# 05__Control_Panel_Items_Sheet.net
KiCad netlist of a schematic drawn in Altium Designer
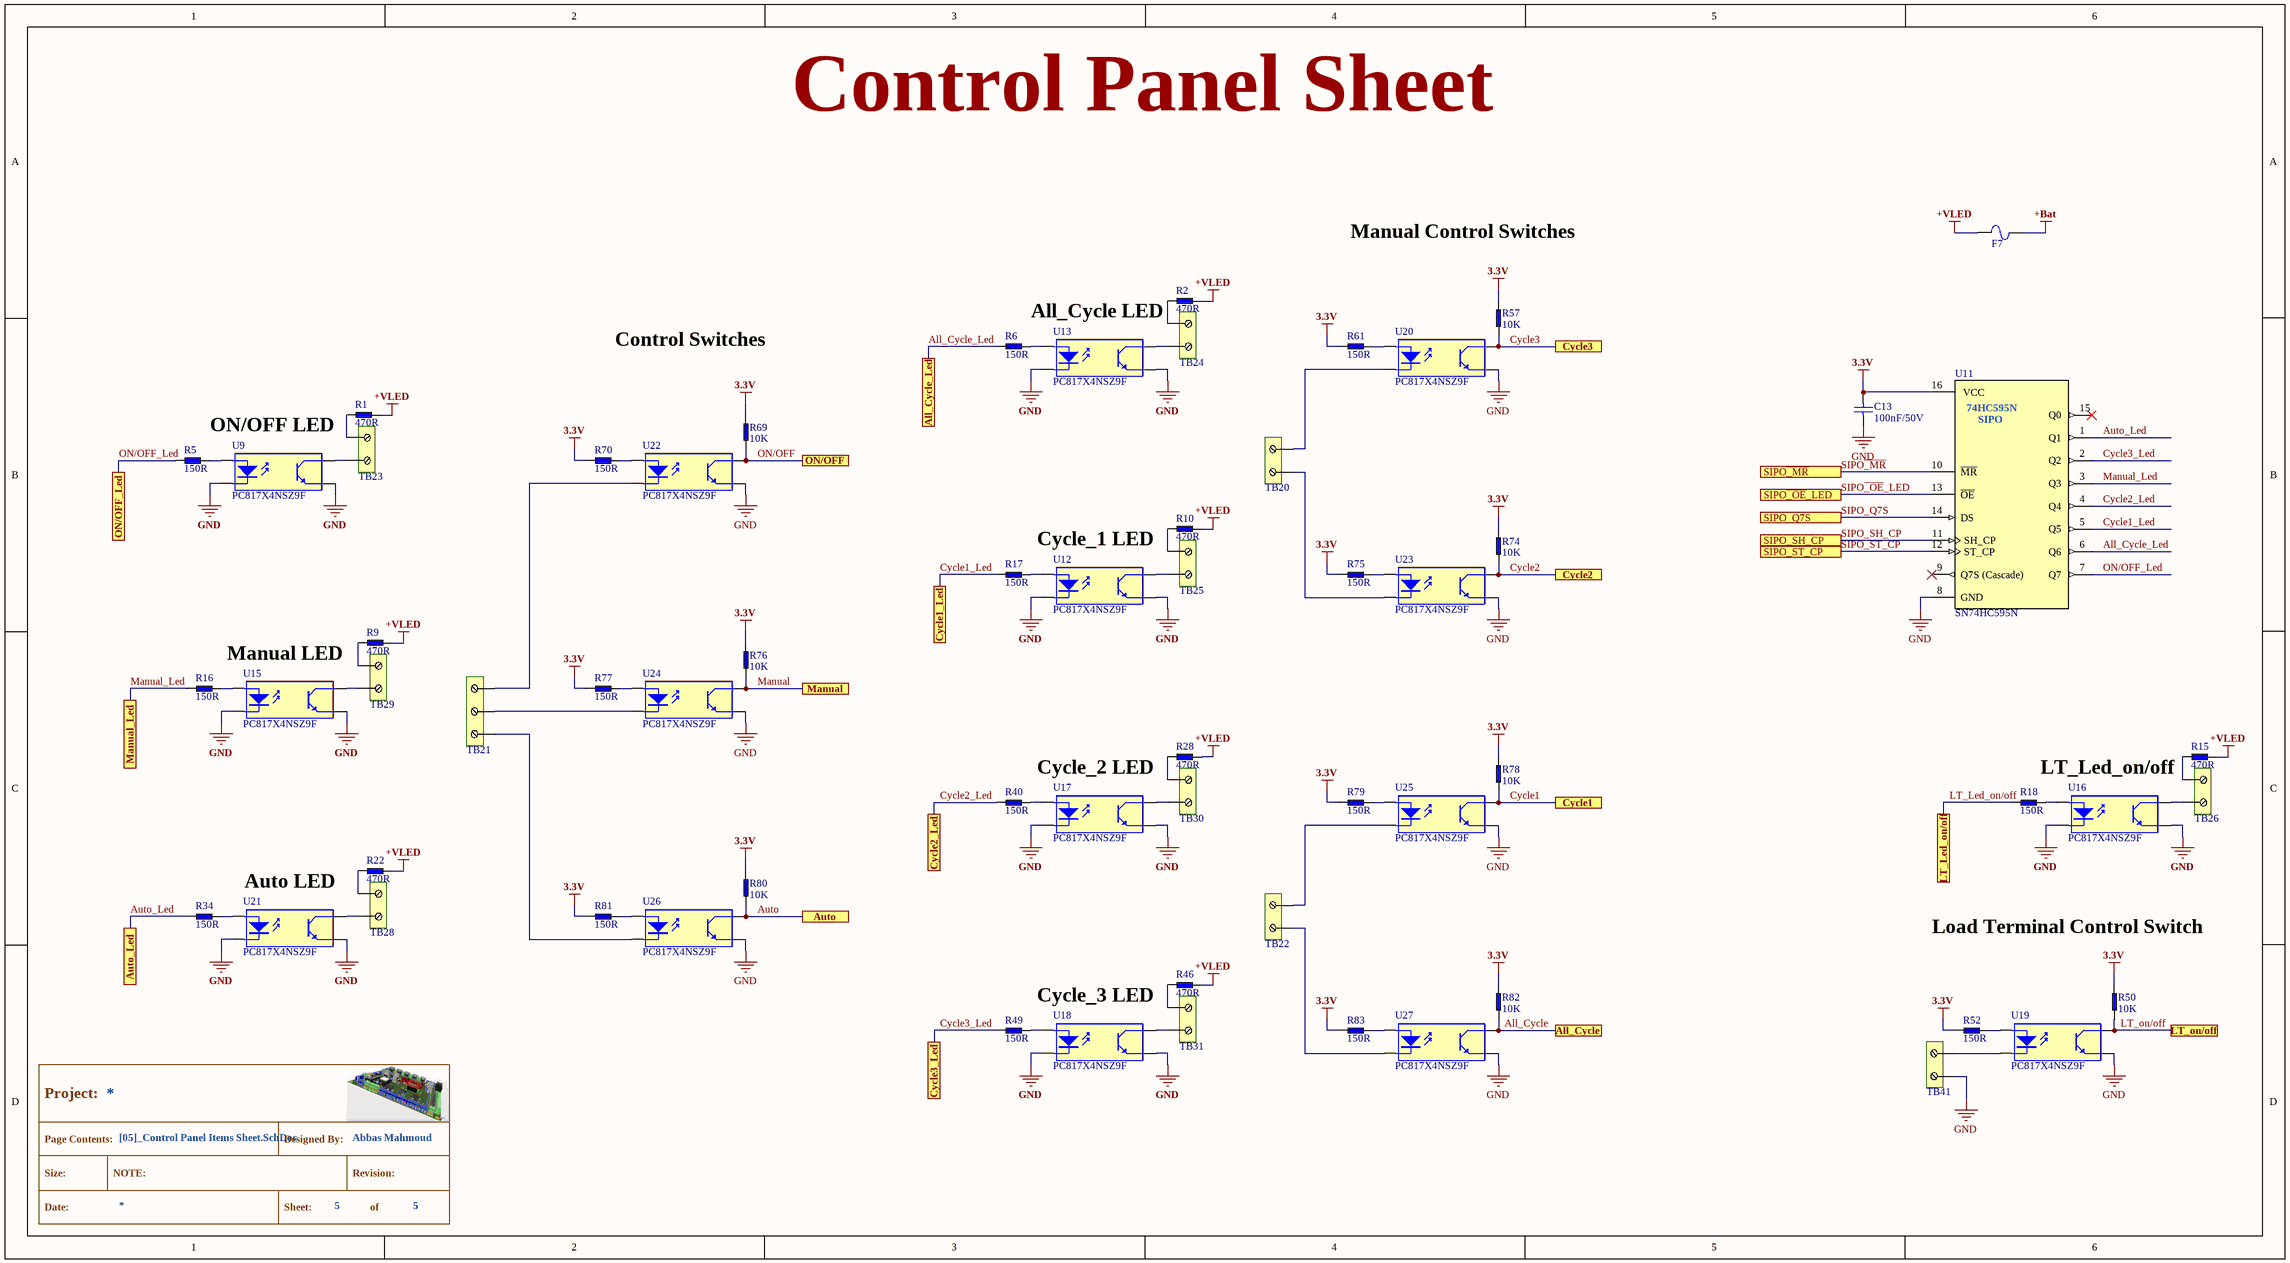
[diagram p0: [05]_Control Panel Items Sheet.SchDoc]

(export (version "E")
  (design (tool "Eeschema 10.0.6"))
  (components
    (comp (ref "*")
      (value "Title Block")
      (description "Moatley Title Block")
      (libsource (lib "Altium_Abbas") (part "Title Block"))
    )
    (comp (ref "C13")
      (value "100nF/50V")
      (footprint "CCAP - PACKAGE - THT ,P = 2.54 MM")
      (description "100nF -20%~+80% 50V Through Hole,P=2.54mm Ceramic Disc Capacitors RoHS")
      (libsource (lib "Altium_Abbas_V3") (part "CCAP - 100nF - 50V - THT - P = 2.54"))
    )
    (comp (ref "F7")
      (value "FUSES&HOLDERS")
      (footprint "FUSE-BLX-A HOLDER")
      (libsource (lib "Altium_Abbas_V3") (part "FUSES&HOLDERS"))
    )
    (comp (ref "R1")
      (value "470R")
      (footprint "R - THT - P5.0 - 1/4W")
      (description "470R ±1% 1/4W ±100ppm/℃ Axial Metal Film Resistor_ Throuh Hole Technology RoHS")
      (libsource (lib "Altium_Abbas_V3") (part "R470R - THT"))
    )
    (comp (ref "R2")
      (value "470R")
      (footprint "R - THT - P5.0 - 1/4W")
      (description "470R ±1% 1/4W ±100ppm/℃ Axial Metal Film Resistor_ Throuh Hole Technology RoHS")
      (libsource (lib "Altium_Abbas_V3") (part "R470R - THT"))
    )
    (comp (ref "R5")
      (value "150R")
      (footprint "R - THT - P5.0 - 1/4W")
      (description "150R ±1% 1/4W ±100ppm/℃ Axial Metal Film Resistor_ Throuh Hole Technology RoHS")
      (libsource (lib "Altium_Abbas_V3") (part "R150R - THT"))
    )
    (comp (ref "R6")
      (value "150R")
      (footprint "R - THT - P5.0 - 1/4W")
      (description "150R ±1% 1/4W ±100ppm/℃ Axial Metal Film Resistor_ Throuh Hole Technology RoHS")
      (libsource (lib "Altium_Abbas_V3") (part "R150R - THT"))
    )
    (comp (ref "R9")
      (value "470R")
      (footprint "R - THT - P5.0 - 1/4W")
      (description "470R ±1% 1/4W ±100ppm/℃ Axial Metal Film Resistor_ Throuh Hole Technology RoHS")
      (libsource (lib "Altium_Abbas_V3") (part "R470R - THT"))
    )
    (comp (ref "R10")
      (value "470R")
      (footprint "R - THT - P5.0 - 1/4W")
      (description "470R ±1% 1/4W ±100ppm/℃ Axial Metal Film Resistor_ Throuh Hole Technology RoHS")
      (libsource (lib "Altium_Abbas_V3") (part "R470R - THT"))
    )
    (comp (ref "R15")
      (value "470R")
      (footprint "R - THT - P5.0 - 1/4W")
      (description "470R ±1% 1/4W ±100ppm/℃ Axial Metal Film Resistor_ Throuh Hole Technology RoHS")
      (libsource (lib "Altium_Abbas_V3") (part "R470R - THT"))
    )
    (comp (ref "R16")
      (value "150R")
      (footprint "R - THT - P5.0 - 1/4W")
      (description "150R ±1% 1/4W ±100ppm/℃ Axial Metal Film Resistor_ Throuh Hole Technology RoHS")
      (libsource (lib "Altium_Abbas_V3") (part "R150R - THT"))
    )
    (comp (ref "R17")
      (value "150R")
      (footprint "R - THT - P5.0 - 1/4W")
      (description "150R ±1% 1/4W ±100ppm/℃ Axial Metal Film Resistor_ Throuh Hole Technology RoHS")
      (libsource (lib "Altium_Abbas_V3") (part "R150R - THT"))
    )
    (comp (ref "R18")
      (value "150R")
      (footprint "R - THT - P5.0 - 1/4W")
      (description "150R ±1% 1/4W ±100ppm/℃ Axial Metal Film Resistor_ Throuh Hole Technology RoHS")
      (libsource (lib "Altium_Abbas_V3") (part "R150R - THT"))
    )
    (comp (ref "R22")
      (value "470R")
      (footprint "R - THT - P5.0 - 1/4W")
      (description "470R ±1% 1/4W ±100ppm/℃ Axial Metal Film Resistor_ Throuh Hole Technology RoHS")
      (libsource (lib "Altium_Abbas_V3") (part "R470R - THT"))
    )
    (comp (ref "R28")
      (value "470R")
      (footprint "R - THT - P5.0 - 1/4W")
      (description "470R ±1% 1/4W ±100ppm/℃ Axial Metal Film Resistor_ Throuh Hole Technology RoHS")
      (libsource (lib "Altium_Abbas_V3") (part "R470R - THT"))
    )
    (comp (ref "R34")
      (value "150R")
      (footprint "R - THT - P5.0 - 1/4W")
      (description "150R ±1% 1/4W ±100ppm/℃ Axial Metal Film Resistor_ Throuh Hole Technology RoHS")
      (libsource (lib "Altium_Abbas_V3") (part "R150R - THT"))
    )
    (comp (ref "R40")
      (value "150R")
      (footprint "R - THT - P5.0 - 1/4W")
      (description "150R ±1% 1/4W ±100ppm/℃ Axial Metal Film Resistor_ Throuh Hole Technology RoHS")
      (libsource (lib "Altium_Abbas_V3") (part "R150R - THT"))
    )
    (comp (ref "R46")
      (value "470R")
      (footprint "R - THT - P5.0 - 1/4W")
      (description "470R ±1% 1/4W ±100ppm/℃ Axial Metal Film Resistor_ Throuh Hole Technology RoHS")
      (libsource (lib "Altium_Abbas_V3") (part "R470R - THT"))
    )
    (comp (ref "R49")
      (value "150R")
      (footprint "R - THT - P5.0 - 1/4W")
      (description "150R ±1% 1/4W ±100ppm/℃ Axial Metal Film Resistor_ Throuh Hole Technology RoHS")
      (libsource (lib "Altium_Abbas_V3") (part "R150R - THT"))
    )
    (comp (ref "R50")
      (value "10K")
      (footprint "R - THT - P5.0 - 1/4W")
      (description "10K ±1% 1/4W ±100ppm/℃ Axial Metal Film Resistor_ Throuh Hole Technology RoHS")
      (libsource (lib "Altium_Abbas_V3") (part "R10K - THT"))
    )
    (comp (ref "R52")
      (value "150R")
      (footprint "R - THT - P5.0 - 1/4W")
      (description "150R ±1% 1/4W ±100ppm/℃ Axial Metal Film Resistor_ Throuh Hole Technology RoHS")
      (libsource (lib "Altium_Abbas_V3") (part "R150R - THT"))
    )
    (comp (ref "R57")
      (value "10K")
      (footprint "R - THT - P5.0 - 1/4W")
      (description "10K ±1% 1/4W ±100ppm/℃ Axial Metal Film Resistor_ Throuh Hole Technology RoHS")
      (libsource (lib "Altium_Abbas_V3") (part "R10K - THT"))
    )
    (comp (ref "R61")
      (value "150R")
      (footprint "R - THT - P5.0 - 1/4W")
      (description "150R ±1% 1/4W ±100ppm/℃ Axial Metal Film Resistor_ Throuh Hole Technology RoHS")
      (libsource (lib "Altium_Abbas_V3") (part "R150R - THT"))
    )
    (comp (ref "R69")
      (value "10K")
      (footprint "R - THT - P5.0 - 1/4W")
      (description "10K ±1% 1/4W ±100ppm/℃ Axial Metal Film Resistor_ Throuh Hole Technology RoHS")
      (libsource (lib "Altium_Abbas_V3") (part "R10K - THT"))
    )
    (comp (ref "R70")
      (value "150R")
      (footprint "R - THT - P5.0 - 1/4W")
      (description "150R ±1% 1/4W ±100ppm/℃ Axial Metal Film Resistor_ Throuh Hole Technology RoHS")
      (libsource (lib "Altium_Abbas_V3") (part "R150R - THT"))
    )
    (comp (ref "R74")
      (value "10K")
      (footprint "R - THT - P5.0 - 1/4W")
      (description "10K ±1% 1/4W ±100ppm/℃ Axial Metal Film Resistor_ Throuh Hole Technology RoHS")
      (libsource (lib "Altium_Abbas_V3") (part "R10K - THT"))
    )
    (comp (ref "R75")
      (value "150R")
      (footprint "R - THT - P5.0 - 1/4W")
      (description "150R ±1% 1/4W ±100ppm/℃ Axial Metal Film Resistor_ Throuh Hole Technology RoHS")
      (libsource (lib "Altium_Abbas_V3") (part "R150R - THT"))
    )
    (comp (ref "R76")
      (value "10K")
      (footprint "R - THT - P5.0 - 1/4W")
      (description "10K ±1% 1/4W ±100ppm/℃ Axial Metal Film Resistor_ Throuh Hole Technology RoHS")
      (libsource (lib "Altium_Abbas_V3") (part "R10K - THT"))
    )
    (comp (ref "R77")
      (value "150R")
      (footprint "R - THT - P5.0 - 1/4W")
      (description "150R ±1% 1/4W ±100ppm/℃ Axial Metal Film Resistor_ Throuh Hole Technology RoHS")
      (libsource (lib "Altium_Abbas_V3") (part "R150R - THT"))
    )
    (comp (ref "R78")
      (value "10K")
      (footprint "R - THT - P5.0 - 1/4W")
      (description "10K ±1% 1/4W ±100ppm/℃ Axial Metal Film Resistor_ Throuh Hole Technology RoHS")
      (libsource (lib "Altium_Abbas_V3") (part "R10K - THT"))
    )
    (comp (ref "R79")
      (value "150R")
      (footprint "R - THT - P5.0 - 1/4W")
      (description "150R ±1% 1/4W ±100ppm/℃ Axial Metal Film Resistor_ Throuh Hole Technology RoHS")
      (libsource (lib "Altium_Abbas_V3") (part "R150R - THT"))
    )
    (comp (ref "R80")
      (value "10K")
      (footprint "R - THT - P5.0 - 1/4W")
      (description "10K ±1% 1/4W ±100ppm/℃ Axial Metal Film Resistor_ Throuh Hole Technology RoHS")
      (libsource (lib "Altium_Abbas_V3") (part "R10K - THT"))
    )
    (comp (ref "R81")
      (value "150R")
      (footprint "R - THT - P5.0 - 1/4W")
      (description "150R ±1% 1/4W ±100ppm/℃ Axial Metal Film Resistor_ Throuh Hole Technology RoHS")
      (libsource (lib "Altium_Abbas_V3") (part "R150R - THT"))
    )
    (comp (ref "R82")
      (value "10K")
      (footprint "R - THT - P5.0 - 1/4W")
      (description "10K ±1% 1/4W ±100ppm/℃ Axial Metal Film Resistor_ Throuh Hole Technology RoHS")
      (libsource (lib "Altium_Abbas_V3") (part "R10K - THT"))
    )
    (comp (ref "R83")
      (value "150R")
      (footprint "R - THT - P5.0 - 1/4W")
      (description "150R ±1% 1/4W ±100ppm/℃ Axial Metal Film Resistor_ Throuh Hole Technology RoHS")
      (libsource (lib "Altium_Abbas_V3") (part "R150R - THT"))
    )
    (comp (ref "TB20")
      (value "2 Pins Pluggable")
      (footprint "TERMINAL BLOCK - 2 PINS - PACKAGE - PLUGGABLE - THT - P = 5.08MM - Horizontal _ Plug+Receptable")
      (libsource (lib "") (part "Terminal Block - 2 Pins - Pluggable_1"))
    )
    (comp (ref "TB21")
      (value "3 Pins Pluggable")
      (footprint "TERMINAL BLOCK - 3 PINS - PACKAGE - PLUGGABLE - THT - P = 5.08MM - HORIZONTAL _ PLUG+RECEPTABLE")
      (libsource (lib "Altium_Abbas_V3") (part "Terminal Block - 3 Pins - Pluggable"))
    )
    (comp (ref "TB22")
      (value "2 Pins Pluggable")
      (footprint "TERMINAL BLOCK - 2 PINS - PACKAGE - PLUGGABLE - THT - P = 5.08MM - Horizontal _ Plug+Receptable")
      (libsource (lib "") (part "Terminal Block - 2 Pins - Pluggable_1"))
    )
    (comp (ref "TB23")
      (value "2 Pins Pluggable")
      (footprint "TERMINAL BLOCK - 2 PINS - PACKAGE - PLUGGABLE - THT - P = 5.08MM - Horizontal _ Plug+Receptable")
      (libsource (lib "Altium_Abbas_V3") (part "Terminal Block - 2 Pins - Pluggable"))
    )
    (comp (ref "TB24")
      (value "2 Pins Pluggable")
      (footprint "TERMINAL BLOCK - 2 PINS - PACKAGE - PLUGGABLE - THT - P = 5.08MM - Horizontal _ Plug+Receptable")
      (libsource (lib "Altium_Abbas_V3") (part "Terminal Block - 2 Pins - Pluggable"))
    )
    (comp (ref "TB25")
      (value "2 Pins Pluggable")
      (footprint "TERMINAL BLOCK - 2 PINS - PACKAGE - PLUGGABLE - THT - P = 5.08MM - Horizontal _ Plug+Receptable")
      (libsource (lib "Altium_Abbas_V3") (part "Terminal Block - 2 Pins - Pluggable"))
    )
    (comp (ref "TB26")
      (value "2 Pins Pluggable")
      (footprint "TERMINAL BLOCK - 2 PINS - PACKAGE - PLUGGABLE - THT - P = 5.08MM - Horizontal _ Plug+Receptable")
      (libsource (lib "Altium_Abbas_V3") (part "Terminal Block - 2 Pins - Pluggable"))
    )
    (comp (ref "TB28")
      (value "2 Pins Pluggable")
      (footprint "TERMINAL BLOCK - 2 PINS - PACKAGE - PLUGGABLE - THT - P = 5.08MM - Horizontal _ Plug+Receptable")
      (libsource (lib "Altium_Abbas_V3") (part "Terminal Block - 2 Pins - Pluggable"))
    )
    (comp (ref "TB29")
      (value "2 Pins Pluggable")
      (footprint "TERMINAL BLOCK - 2 PINS - PACKAGE - PLUGGABLE - THT - P = 5.08MM - Horizontal _ Plug+Receptable")
      (libsource (lib "Altium_Abbas_V3") (part "Terminal Block - 2 Pins - Pluggable"))
    )
    (comp (ref "TB30")
      (value "2 Pins Pluggable")
      (footprint "TERMINAL BLOCK - 2 PINS - PACKAGE - PLUGGABLE - THT - P = 5.08MM - Horizontal _ Plug+Receptable")
      (libsource (lib "Altium_Abbas_V3") (part "Terminal Block - 2 Pins - Pluggable"))
    )
    (comp (ref "TB31")
      (value "2 Pins Pluggable")
      (footprint "TERMINAL BLOCK - 2 PINS - PACKAGE - PLUGGABLE - THT - P = 5.08MM - Horizontal _ Plug+Receptable")
      (libsource (lib "Altium_Abbas_V3") (part "Terminal Block - 2 Pins - Pluggable"))
    )
    (comp (ref "TB41")
      (value "2 Pins Pluggable")
      (footprint "TERMINAL BLOCK - 2 PINS - PACKAGE - PLUGGABLE - THT - P = 5.08MM - Horizontal _ Plug+Receptable")
      (libsource (lib "") (part "Terminal Block - 2 Pins - Pluggable_1"))
    )
    (comp (ref "U9")
      (value "PC817X4NSZ9F")
      (footprint "ICB - DIP-4")
      (description "Optoisolator Transistor Output 5000Vrms 1 Channel 4-DIP")
      (fields (field (name "MANUFACTURER") "Sharp Microelectronics"))
      (libsource (lib "Altium_Abbas_V3") (part "IC - PC817X4NSZ9F"))
    )
    (comp (ref "U11")
      (value "SN74HC595N")
      (footprint "ICB - DIP-16")
      (description "Serial to Parallel or Serial Shift Register Supplementary type DIP-16 Shift Registers RoHS")
      (fields (field (name "MANUFACTURER") "Texas Instruments"))
      (libsource (lib "Altium_Abbas_V3") (part "IC - SN74HC595N"))
    )
    (comp (ref "U12")
      (value "PC817X4NSZ9F")
      (footprint "ICB - DIP-4")
      (description "Optoisolator Transistor Output 5000Vrms 1 Channel 4-DIP")
      (fields (field (name "MANUFACTURER") "Sharp Microelectronics"))
      (libsource (lib "Altium_Abbas_V3") (part "IC - PC817X4NSZ9F"))
    )
    (comp (ref "U13")
      (value "PC817X4NSZ9F")
      (footprint "ICB - DIP-4")
      (description "Optoisolator Transistor Output 5000Vrms 1 Channel 4-DIP")
      (fields (field (name "MANUFACTURER") "Sharp Microelectronics"))
      (libsource (lib "Altium_Abbas_V3") (part "IC - PC817X4NSZ9F"))
    )
    (comp (ref "U15")
      (value "PC817X4NSZ9F")
      (footprint "ICB - DIP-4")
      (description "Optoisolator Transistor Output 5000Vrms 1 Channel 4-DIP")
      (fields (field (name "MANUFACTURER") "Sharp Microelectronics"))
      (libsource (lib "Altium_Abbas_V3") (part "IC - PC817X4NSZ9F"))
    )
    (comp (ref "U16")
      (value "PC817X4NSZ9F")
      (footprint "ICB - DIP-4")
      (description "Optoisolator Transistor Output 5000Vrms 1 Channel 4-DIP")
      (fields (field (name "MANUFACTURER") "Sharp Microelectronics"))
      (libsource (lib "Altium_Abbas_V3") (part "IC - PC817X4NSZ9F"))
    )
    (comp (ref "U17")
      (value "PC817X4NSZ9F")
      (footprint "ICB - DIP-4")
      (description "Optoisolator Transistor Output 5000Vrms 1 Channel 4-DIP")
      (fields (field (name "MANUFACTURER") "Sharp Microelectronics"))
      (libsource (lib "Altium_Abbas_V3") (part "IC - PC817X4NSZ9F"))
    )
    (comp (ref "U18")
      (value "PC817X4NSZ9F")
      (footprint "ICB - DIP-4")
      (description "Optoisolator Transistor Output 5000Vrms 1 Channel 4-DIP")
      (fields (field (name "MANUFACTURER") "Sharp Microelectronics"))
      (libsource (lib "Altium_Abbas_V3") (part "IC - PC817X4NSZ9F"))
    )
    (comp (ref "U19")
      (value "PC817X4NSZ9F")
      (footprint "ICB - DIP-4")
      (description "Optoisolator Transistor Output 5000Vrms 1 Channel 4-DIP")
      (fields (field (name "MANUFACTURER") "Sharp Microelectronics"))
      (libsource (lib "Altium_Abbas_V3") (part "IC - PC817X4NSZ9F"))
    )
    (comp (ref "U20")
      (value "PC817X4NSZ9F")
      (footprint "ICB - DIP-4")
      (description "Optoisolator Transistor Output 5000Vrms 1 Channel 4-DIP")
      (fields (field (name "MANUFACTURER") "Sharp Microelectronics"))
      (libsource (lib "Altium_Abbas_V3") (part "IC - PC817X4NSZ9F"))
    )
    (comp (ref "U21")
      (value "PC817X4NSZ9F")
      (footprint "ICB - DIP-4")
      (description "Optoisolator Transistor Output 5000Vrms 1 Channel 4-DIP")
      (fields (field (name "MANUFACTURER") "Sharp Microelectronics"))
      (libsource (lib "Altium_Abbas_V3") (part "IC - PC817X4NSZ9F"))
    )
    (comp (ref "U22")
      (value "PC817X4NSZ9F")
      (footprint "ICB - DIP-4")
      (description "Optoisolator Transistor Output 5000Vrms 1 Channel 4-DIP")
      (fields (field (name "MANUFACTURER") "Sharp Microelectronics"))
      (libsource (lib "Altium_Abbas_V3") (part "IC - PC817X4NSZ9F"))
    )
    (comp (ref "U23")
      (value "PC817X4NSZ9F")
      (footprint "ICB - DIP-4")
      (description "Optoisolator Transistor Output 5000Vrms 1 Channel 4-DIP")
      (fields (field (name "MANUFACTURER") "Sharp Microelectronics"))
      (libsource (lib "Altium_Abbas_V3") (part "IC - PC817X4NSZ9F"))
    )
    (comp (ref "U24")
      (value "PC817X4NSZ9F")
      (footprint "ICB - DIP-4")
      (description "Optoisolator Transistor Output 5000Vrms 1 Channel 4-DIP")
      (fields (field (name "MANUFACTURER") "Sharp Microelectronics"))
      (libsource (lib "Altium_Abbas_V3") (part "IC - PC817X4NSZ9F"))
    )
    (comp (ref "U25")
      (value "PC817X4NSZ9F")
      (footprint "ICB - DIP-4")
      (description "Optoisolator Transistor Output 5000Vrms 1 Channel 4-DIP")
      (fields (field (name "MANUFACTURER") "Sharp Microelectronics"))
      (libsource (lib "Altium_Abbas_V3") (part "IC - PC817X4NSZ9F"))
    )
    (comp (ref "U26")
      (value "PC817X4NSZ9F")
      (footprint "ICB - DIP-4")
      (description "Optoisolator Transistor Output 5000Vrms 1 Channel 4-DIP")
      (fields (field (name "MANUFACTURER") "Sharp Microelectronics"))
      (libsource (lib "Altium_Abbas_V3") (part "IC - PC817X4NSZ9F"))
    )
    (comp (ref "U27")
      (value "PC817X4NSZ9F")
      (footprint "ICB - DIP-4")
      (description "Optoisolator Transistor Output 5000Vrms 1 Channel 4-DIP")
      (fields (field (name "MANUFACTURER") "Sharp Microelectronics"))
      (libsource (lib "Altium_Abbas_V3") (part "IC - PC817X4NSZ9F"))
    )
  )
  (nets
    (net (code "1") (name "+Bat") (class "Default") (node (ref "F7") (pin "2") (pintype "passive")))
    (net (code "2") (name "+VLED") (class "Default")
      (node (ref "F7") (pin "1") (pintype "passive"))
      (node (ref "R1") (pin "2") (pinfunction "6_2") (pintype "passive"))
      (node (ref "R10") (pin "2") (pinfunction "6_2") (pintype "passive"))
      (node (ref "R15") (pin "2") (pinfunction "6_2") (pintype "passive"))
      (node (ref "R2") (pin "2") (pinfunction "6_2") (pintype "passive"))
      (node (ref "R22") (pin "2") (pinfunction "6_2") (pintype "passive"))
      (node (ref "R28") (pin "2") (pinfunction "6_2") (pintype "passive"))
      (node (ref "R46") (pin "2") (pinfunction "6_2") (pintype "passive"))
      (node (ref "R9") (pin "2") (pinfunction "6_2") (pintype "passive"))
    )
    (net (code "3") (name "/All_Cycle") (class "Default")
      (node (ref "R82") (pin "1") (pinfunction "5_1") (pintype "passive"))
      (node (ref "U27") (pin "4") (pinfunction "C_4") (pintype "passive"))
    )
    (net (code "4") (name "/All_Cycle_Led") (class "Default")
      (node (ref "R6") (pin "1") (pinfunction "5_1") (pintype "passive"))
      (node (ref "U11") (pin "6") (pinfunction "Q6_6") (pintype "output"))
    )
    (net (code "5") (name "/Auto") (class "Default")
      (node (ref "R80") (pin "1") (pinfunction "5_1") (pintype "passive"))
      (node (ref "U26") (pin "4") (pinfunction "C_4") (pintype "passive"))
    )
    (net (code "6") (name "/Auto_Led") (class "Default")
      (node (ref "R34") (pin "1") (pinfunction "5_1") (pintype "passive"))
      (node (ref "U11") (pin "1") (pinfunction "Q1_1") (pintype "output"))
    )
    (net (code "7") (name "/Cycle1") (class "Default")
      (node (ref "R78") (pin "1") (pinfunction "5_1") (pintype "passive"))
      (node (ref "U25") (pin "4") (pinfunction "C_4") (pintype "passive"))
    )
    (net (code "8") (name "/Cycle1_Led") (class "Default")
      (node (ref "R17") (pin "1") (pinfunction "5_1") (pintype "passive"))
      (node (ref "U11") (pin "5") (pinfunction "Q5_5") (pintype "output"))
    )
    (net (code "9") (name "/Cycle2") (class "Default")
      (node (ref "R74") (pin "1") (pinfunction "5_1") (pintype "passive"))
      (node (ref "U23") (pin "4") (pinfunction "C_4") (pintype "passive"))
    )
    (net (code "10") (name "/Cycle2_Led") (class "Default")
      (node (ref "R40") (pin "1") (pinfunction "5_1") (pintype "passive"))
      (node (ref "U11") (pin "4") (pinfunction "Q4_4") (pintype "output"))
    )
    (net (code "11") (name "/Cycle3") (class "Default")
      (node (ref "R57") (pin "1") (pinfunction "5_1") (pintype "passive"))
      (node (ref "U20") (pin "4") (pinfunction "C_4") (pintype "passive"))
    )
    (net (code "12") (name "/Cycle3_Led") (class "Default")
      (node (ref "R49") (pin "1") (pinfunction "5_1") (pintype "passive"))
      (node (ref "U11") (pin "2") (pinfunction "Q2_2") (pintype "output"))
    )
    (net (code "13") (name "/LT_Led_on{slash}off") (class "Default")
      (node (ref "R18") (pin "1") (pinfunction "5_1") (pintype "passive"))
    )
    (net (code "14") (name "/LT_on{slash}off") (class "Default")
      (node (ref "R50") (pin "1") (pinfunction "5_1") (pintype "passive"))
      (node (ref "U19") (pin "4") (pinfunction "C_4") (pintype "passive"))
    )
    (net (code "15") (name "/Manual") (class "Default")
      (node (ref "R76") (pin "1") (pinfunction "5_1") (pintype "passive"))
      (node (ref "U24") (pin "4") (pinfunction "C_4") (pintype "passive"))
    )
    (net (code "16") (name "/Manual_Led") (class "Default")
      (node (ref "R16") (pin "1") (pinfunction "5_1") (pintype "passive"))
      (node (ref "U11") (pin "3") (pinfunction "Q3_3") (pintype "output"))
    )
    (net (code "17") (name "/ON{slash}OFF") (class "Default")
      (node (ref "R69") (pin "1") (pinfunction "5_1") (pintype "passive"))
      (node (ref "U22") (pin "4") (pinfunction "C_4") (pintype "passive"))
    )
    (net (code "18") (name "/ON{slash}OFF_Led") (class "Default")
      (node (ref "R5") (pin "1") (pinfunction "5_1") (pintype "passive"))
      (node (ref "U11") (pin "7") (pinfunction "Q7_7") (pintype "output"))
    )
    (net (code "19") (name "/SIPO_Q7S") (class "Default")
      (node (ref "U11") (pin "14") (pinfunction "DS_14") (pintype "input"))
    )
    (net (code "20") (name "/SIPO_SH_CP") (class "Default")
      (node (ref "U11") (pin "11") (pinfunction "SH_CP_11") (pintype "input"))
    )
    (net (code "21") (name "/SIPO_ST_CP") (class "Default")
      (node (ref "U11") (pin "12") (pinfunction "ST_CP_12") (pintype "input"))
    )
    (net (code "22") (name "/SIPO~{_MR}") (class "Default")
      (node (ref "U11") (pin "10") (pinfunction "~{MR}_10") (pintype "passive"))
    )
    (net (code "23") (name "/SIPO~{_OE}_LED") (class "Default")
      (node (ref "U11") (pin "13") (pinfunction "~{OE}_13") (pintype "passive"))
    )
    (net (code "24") (name "3.3V") (class "Default")
      (node (ref "C13") (pin "1") (pinfunction "1_1") (pintype "passive"))
      (node (ref "R50") (pin "2") (pinfunction "6_2") (pintype "passive"))
      (node (ref "R52") (pin "1") (pinfunction "5_1") (pintype "passive"))
      (node (ref "R57") (pin "2") (pinfunction "6_2") (pintype "passive"))
      (node (ref "R61") (pin "1") (pinfunction "5_1") (pintype "passive"))
      (node (ref "R69") (pin "2") (pinfunction "6_2") (pintype "passive"))
      (node (ref "R70") (pin "1") (pinfunction "5_1") (pintype "passive"))
      (node (ref "R74") (pin "2") (pinfunction "6_2") (pintype "passive"))
      (node (ref "R75") (pin "1") (pinfunction "5_1") (pintype "passive"))
      (node (ref "R76") (pin "2") (pinfunction "6_2") (pintype "passive"))
      (node (ref "R77") (pin "1") (pinfunction "5_1") (pintype "passive"))
      (node (ref "R78") (pin "2") (pinfunction "6_2") (pintype "passive"))
      (node (ref "R79") (pin "1") (pinfunction "5_1") (pintype "passive"))
      (node (ref "R80") (pin "2") (pinfunction "6_2") (pintype "passive"))
      (node (ref "R81") (pin "1") (pinfunction "5_1") (pintype "passive"))
      (node (ref "R82") (pin "2") (pinfunction "6_2") (pintype "passive"))
      (node (ref "R83") (pin "1") (pinfunction "5_1") (pintype "passive"))
      (node (ref "U11") (pin "16") (pinfunction "VCC_16") (pintype "passive"))
    )
    (net (code "25") (name "GND") (class "Default")
      (node (ref "C13") (pin "2") (pinfunction "2_2") (pintype "passive"))
      (node (ref "TB41") (pin "1") (pinfunction "1_1") (pintype "passive"))
      (node (ref "U11") (pin "8") (pinfunction "GND_8") (pintype "passive"))
      (node (ref "U12") (pin "2") (pinfunction "K_2") (pintype "passive"))
      (node (ref "U12") (pin "3") (pinfunction "E_3") (pintype "passive"))
      (node (ref "U13") (pin "2") (pinfunction "K_2") (pintype "passive"))
      (node (ref "U13") (pin "3") (pinfunction "E_3") (pintype "passive"))
      (node (ref "U15") (pin "2") (pinfunction "K_2") (pintype "passive"))
      (node (ref "U15") (pin "3") (pinfunction "E_3") (pintype "passive"))
      (node (ref "U16") (pin "2") (pinfunction "K_2") (pintype "passive"))
      (node (ref "U16") (pin "3") (pinfunction "E_3") (pintype "passive"))
      (node (ref "U17") (pin "2") (pinfunction "K_2") (pintype "passive"))
      (node (ref "U17") (pin "3") (pinfunction "E_3") (pintype "passive"))
      (node (ref "U18") (pin "2") (pinfunction "K_2") (pintype "passive"))
      (node (ref "U18") (pin "3") (pinfunction "E_3") (pintype "passive"))
      (node (ref "U19") (pin "3") (pinfunction "E_3") (pintype "passive"))
      (node (ref "U20") (pin "3") (pinfunction "E_3") (pintype "passive"))
      (node (ref "U21") (pin "2") (pinfunction "K_2") (pintype "passive"))
      (node (ref "U21") (pin "3") (pinfunction "E_3") (pintype "passive"))
      (node (ref "U22") (pin "3") (pinfunction "E_3") (pintype "passive"))
      (node (ref "U23") (pin "3") (pinfunction "E_3") (pintype "passive"))
      (node (ref "U24") (pin "3") (pinfunction "E_3") (pintype "passive"))
      (node (ref "U25") (pin "3") (pinfunction "E_3") (pintype "passive"))
      (node (ref "U26") (pin "3") (pinfunction "E_3") (pintype "passive"))
      (node (ref "U27") (pin "3") (pinfunction "E_3") (pintype "passive"))
      (node (ref "U9") (pin "2") (pinfunction "K_2") (pintype "passive"))
      (node (ref "U9") (pin "3") (pinfunction "E_3") (pintype "passive"))
    )
    (net (code "26") (name "Net-(R1-5)") (class "Default")
      (node (ref "R1") (pin "1") (pinfunction "5_1") (pintype "passive"))
      (node (ref "TB23") (pin "2") (pinfunction "2_2") (pintype "passive"))
    )
    (net (code "27") (name "Net-(R2-5)") (class "Default")
      (node (ref "R2") (pin "1") (pinfunction "5_1") (pintype "passive"))
      (node (ref "TB24") (pin "2") (pinfunction "2_2") (pintype "passive"))
    )
    (net (code "28") (name "Net-(R5-6)") (class "Default")
      (node (ref "R5") (pin "2") (pinfunction "6_2") (pintype "passive"))
      (node (ref "U9") (pin "1") (pinfunction "A_1") (pintype "passive"))
    )
    (net (code "29") (name "Net-(R6-6)") (class "Default")
      (node (ref "R6") (pin "2") (pinfunction "6_2") (pintype "passive"))
      (node (ref "U13") (pin "1") (pinfunction "A_1") (pintype "passive"))
    )
    (net (code "30") (name "Net-(R9-5)") (class "Default")
      (node (ref "R9") (pin "1") (pinfunction "5_1") (pintype "passive"))
      (node (ref "TB29") (pin "2") (pinfunction "2_2") (pintype "passive"))
    )
    (net (code "31") (name "Net-(R10-5)") (class "Default")
      (node (ref "R10") (pin "1") (pinfunction "5_1") (pintype "passive"))
      (node (ref "TB25") (pin "2") (pinfunction "2_2") (pintype "passive"))
    )
    (net (code "32") (name "Net-(R15-5)") (class "Default")
      (node (ref "R15") (pin "1") (pinfunction "5_1") (pintype "passive"))
      (node (ref "TB26") (pin "2") (pinfunction "2_2") (pintype "passive"))
    )
    (net (code "33") (name "Net-(R16-6)") (class "Default")
      (node (ref "R16") (pin "2") (pinfunction "6_2") (pintype "passive"))
      (node (ref "U15") (pin "1") (pinfunction "A_1") (pintype "passive"))
    )
    (net (code "34") (name "Net-(R17-6)") (class "Default")
      (node (ref "R17") (pin "2") (pinfunction "6_2") (pintype "passive"))
      (node (ref "U12") (pin "1") (pinfunction "A_1") (pintype "passive"))
    )
    (net (code "35") (name "Net-(R18-6)") (class "Default")
      (node (ref "R18") (pin "2") (pinfunction "6_2") (pintype "passive"))
      (node (ref "U16") (pin "1") (pinfunction "A_1") (pintype "passive"))
    )
    (net (code "36") (name "Net-(R22-5)") (class "Default")
      (node (ref "R22") (pin "1") (pinfunction "5_1") (pintype "passive"))
      (node (ref "TB28") (pin "2") (pinfunction "2_2") (pintype "passive"))
    )
    (net (code "37") (name "Net-(R28-5)") (class "Default")
      (node (ref "R28") (pin "1") (pinfunction "5_1") (pintype "passive"))
      (node (ref "TB30") (pin "2") (pinfunction "2_2") (pintype "passive"))
    )
    (net (code "38") (name "Net-(R34-6)") (class "Default")
      (node (ref "R34") (pin "2") (pinfunction "6_2") (pintype "passive"))
      (node (ref "U21") (pin "1") (pinfunction "A_1") (pintype "passive"))
    )
    (net (code "39") (name "Net-(R40-6)") (class "Default")
      (node (ref "R40") (pin "2") (pinfunction "6_2") (pintype "passive"))
      (node (ref "U17") (pin "1") (pinfunction "A_1") (pintype "passive"))
    )
    (net (code "40") (name "Net-(R46-5)") (class "Default")
      (node (ref "R46") (pin "1") (pinfunction "5_1") (pintype "passive"))
      (node (ref "TB31") (pin "2") (pinfunction "2_2") (pintype "passive"))
    )
    (net (code "41") (name "Net-(R49-6)") (class "Default")
      (node (ref "R49") (pin "2") (pinfunction "6_2") (pintype "passive"))
      (node (ref "U18") (pin "1") (pinfunction "A_1") (pintype "passive"))
    )
    (net (code "42") (name "Net-(R52-6)") (class "Default")
      (node (ref "R52") (pin "2") (pinfunction "6_2") (pintype "passive"))
      (node (ref "U19") (pin "1") (pinfunction "A_1") (pintype "passive"))
    )
    (net (code "43") (name "Net-(R61-6)") (class "Default")
      (node (ref "R61") (pin "2") (pinfunction "6_2") (pintype "passive"))
      (node (ref "U20") (pin "1") (pinfunction "A_1") (pintype "passive"))
    )
    (net (code "44") (name "Net-(R70-6)") (class "Default")
      (node (ref "R70") (pin "2") (pinfunction "6_2") (pintype "passive"))
      (node (ref "U22") (pin "1") (pinfunction "A_1") (pintype "passive"))
    )
    (net (code "45") (name "Net-(R75-6)") (class "Default")
      (node (ref "R75") (pin "2") (pinfunction "6_2") (pintype "passive"))
      (node (ref "U23") (pin "1") (pinfunction "A_1") (pintype "passive"))
    )
    (net (code "46") (name "Net-(R77-6)") (class "Default")
      (node (ref "R77") (pin "2") (pinfunction "6_2") (pintype "passive"))
      (node (ref "U24") (pin "1") (pinfunction "A_1") (pintype "passive"))
    )
    (net (code "47") (name "Net-(R79-6)") (class "Default")
      (node (ref "R79") (pin "2") (pinfunction "6_2") (pintype "passive"))
      (node (ref "U25") (pin "1") (pinfunction "A_1") (pintype "passive"))
    )
    (net (code "48") (name "Net-(R81-6)") (class "Default")
      (node (ref "R81") (pin "2") (pinfunction "6_2") (pintype "passive"))
      (node (ref "U26") (pin "1") (pinfunction "A_1") (pintype "passive"))
    )
    (net (code "49") (name "Net-(R83-6)") (class "Default")
      (node (ref "R83") (pin "2") (pinfunction "6_2") (pintype "passive"))
      (node (ref "U27") (pin "1") (pinfunction "A_1") (pintype "passive"))
    )
    (net (code "50") (name "Net-(U9-C)") (class "Default")
      (node (ref "TB23") (pin "1") (pinfunction "1_1") (pintype "passive"))
      (node (ref "U9") (pin "4") (pinfunction "C_4") (pintype "passive"))
    )
    (net (code "51") (name "Net-(U12-C)") (class "Default")
      (node (ref "TB25") (pin "1") (pinfunction "1_1") (pintype "passive"))
      (node (ref "U12") (pin "4") (pinfunction "C_4") (pintype "passive"))
    )
    (net (code "52") (name "Net-(U13-C)") (class "Default")
      (node (ref "TB24") (pin "1") (pinfunction "1_1") (pintype "passive"))
      (node (ref "U13") (pin "4") (pinfunction "C_4") (pintype "passive"))
    )
    (net (code "53") (name "Net-(U15-C)") (class "Default")
      (node (ref "TB29") (pin "1") (pinfunction "1_1") (pintype "passive"))
      (node (ref "U15") (pin "4") (pinfunction "C_4") (pintype "passive"))
    )
    (net (code "54") (name "Net-(U16-C)") (class "Default")
      (node (ref "TB26") (pin "1") (pinfunction "1_1") (pintype "passive"))
      (node (ref "U16") (pin "4") (pinfunction "C_4") (pintype "passive"))
    )
    (net (code "55") (name "Net-(U17-C)") (class "Default")
      (node (ref "TB30") (pin "1") (pinfunction "1_1") (pintype "passive"))
      (node (ref "U17") (pin "4") (pinfunction "C_4") (pintype "passive"))
    )
    (net (code "56") (name "Net-(U18-C)") (class "Default")
      (node (ref "TB31") (pin "1") (pinfunction "1_1") (pintype "passive"))
      (node (ref "U18") (pin "4") (pinfunction "C_4") (pintype "passive"))
    )
    (net (code "57") (name "Net-(U19-K)") (class "Default")
      (node (ref "TB41") (pin "2") (pinfunction "2_2") (pintype "passive"))
      (node (ref "U19") (pin "2") (pinfunction "K_2") (pintype "passive"))
    )
    (net (code "58") (name "Net-(U20-K)") (class "Default")
      (node (ref "TB20") (pin "2") (pinfunction "2_2") (pintype "passive"))
      (node (ref "U20") (pin "2") (pinfunction "K_2") (pintype "passive"))
    )
    (net (code "59") (name "Net-(U21-C)") (class "Default")
      (node (ref "TB28") (pin "1") (pinfunction "1_1") (pintype "passive"))
      (node (ref "U21") (pin "4") (pinfunction "C_4") (pintype "passive"))
    )
    (net (code "60") (name "Net-(U22-K)") (class "Default")
      (node (ref "TB21") (pin "3") (pinfunction "3_3") (pintype "passive"))
      (node (ref "U22") (pin "2") (pinfunction "K_2") (pintype "passive"))
    )
    (net (code "61") (name "Net-(U23-K)") (class "Default")
      (node (ref "TB20") (pin "1") (pinfunction "1_1") (pintype "passive"))
      (node (ref "U23") (pin "2") (pinfunction "K_2") (pintype "passive"))
    )
    (net (code "62") (name "Net-(U24-K)") (class "Default")
      (node (ref "TB21") (pin "2") (pinfunction "2_2") (pintype "passive"))
      (node (ref "U24") (pin "2") (pinfunction "K_2") (pintype "passive"))
    )
    (net (code "63") (name "Net-(U25-K)") (class "Default")
      (node (ref "TB22") (pin "2") (pinfunction "2_2") (pintype "passive"))
      (node (ref "U25") (pin "2") (pinfunction "K_2") (pintype "passive"))
    )
    (net (code "64") (name "Net-(U26-K)") (class "Default")
      (node (ref "TB21") (pin "1") (pinfunction "1_1") (pintype "passive"))
      (node (ref "U26") (pin "2") (pinfunction "K_2") (pintype "passive"))
    )
    (net (code "65") (name "Net-(U27-K)") (class "Default")
      (node (ref "TB22") (pin "1") (pinfunction "1_1") (pintype "passive"))
      (node (ref "U27") (pin "2") (pinfunction "K_2") (pintype "passive"))
    )
    (net (code "66") (name "unconnected-(U11-Q0-Pad15)") (class "Default")
      (node (ref "U11") (pin "15") (pinfunction "Q0_15") (pintype "output+no_connect"))
    )
    (net (code "67") (name "unconnected-(U11-Q7S_(Cascade)-Pad9)") (class "Default")
      (node (ref "U11") (pin "9") (pinfunction "Q7S_(Cascade)_9") (pintype "output+no_connect"))
    )
  )
)
